# ISL6236A_DEMO.net
KiCad netlist of a schematic drawn in Altium Designer
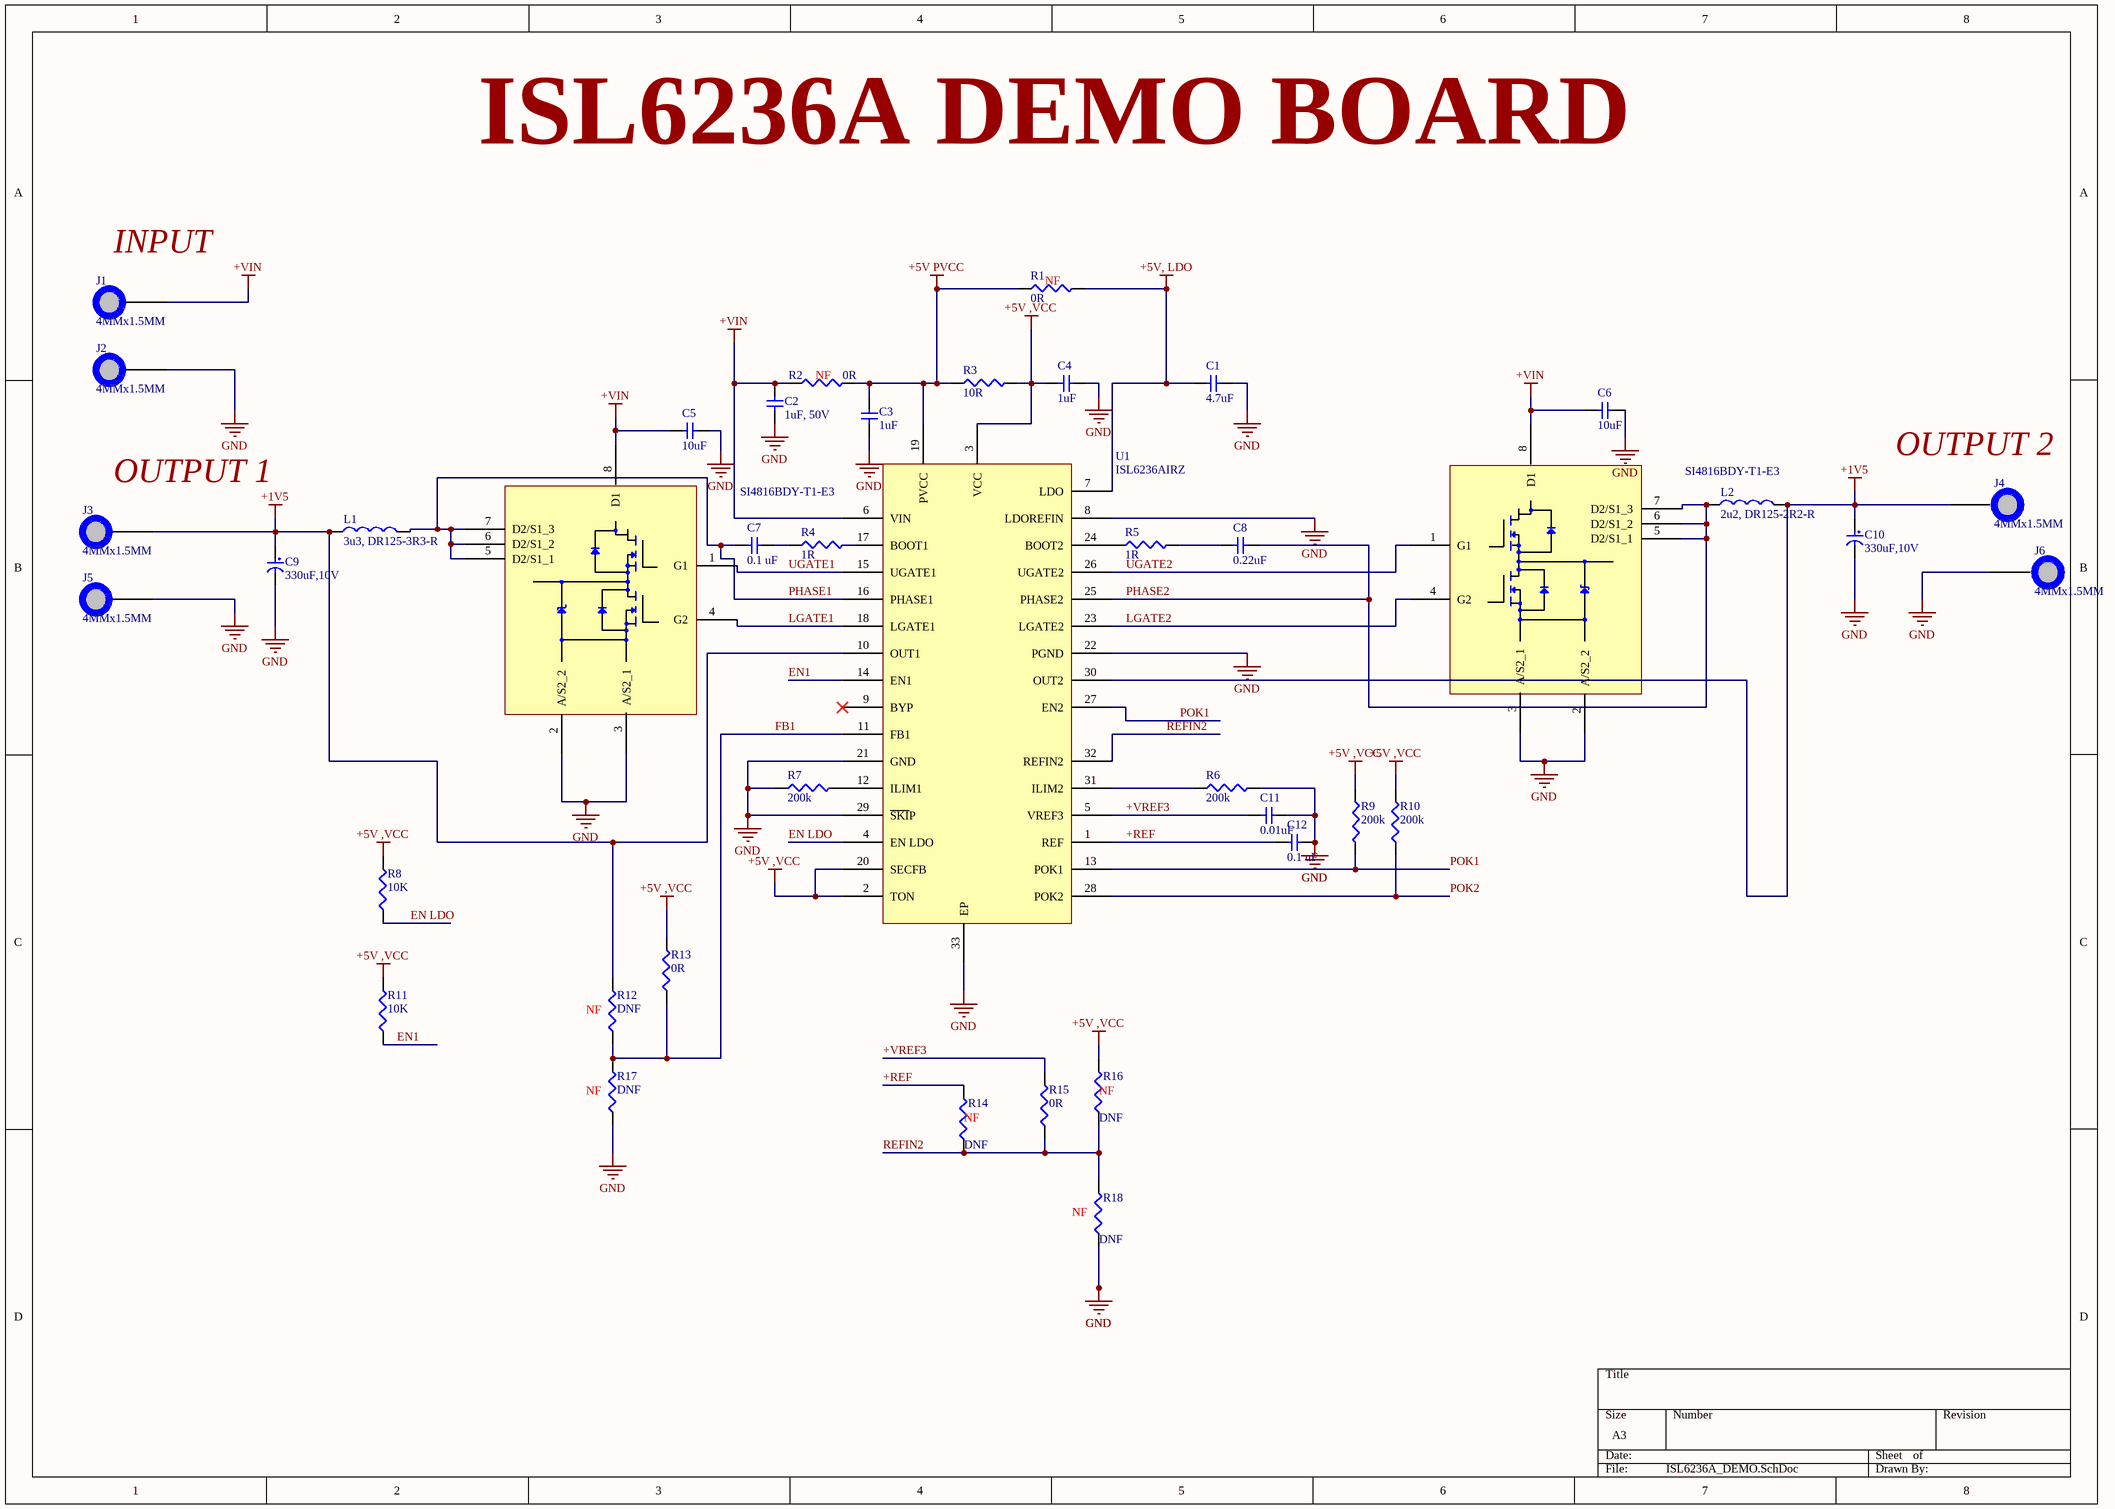
[diagram p0: ISL6236A_DEMO.SchDoc]

(export (version "E")
  (design (tool "Eeschema 10.0.6"))
  (components
    (comp (ref "C1")
      (value "4.7uF")
      (footprint "C1206")
      (description "C Series 1206 4.7 uF 50 V ±10 % Tolerance X5R SMT Multilayer Ceramic Capacitor")
      (fields
        (field (name "MANUFACTURER") "TDK")
        (field (name "MANUFACTURER PART NUMBER") "C3216X5R1H475K160AB")
      )
      (libsource (lib "ISL6236A_DEMO_V1I1") (part "C3216X5R1H475K160AB"))
    )
    (comp (ref "C2")
      (value "1uF, 50V")
      (footprint "C0805")
      (fields
        (field (name "MANUFACTURER") "KEMET")
        (field (name "MANUFACTURER PART NUMBER") "C0805X105K5RACAUTO")
      )
      (libsource (lib "ISL6236A_DEMO_V1I1") (part "C0805X105K5RACAUTO"))
    )
    (comp (ref "C3")
      (value "1uF")
      (footprint "C0805")
      (description "Cap Cer 1UF 25V X5R 0805")
      (fields
        (field (name "MANUFACTURER") "Kyocera AVX")
        (field (name "MANUFACTURER PART NUMBER") "08053D105KAT2~{A}3K")
      )
      (libsource (lib "ISL6236A_DEMO_V1I1") (part "08053D105KAT2A{backslash}3K"))
    )
    (comp (ref "C4")
      (value "1uF")
      (footprint "C0805")
      (description "Cap Cer 1UF 25V X5R 0805")
      (fields
        (field (name "MANUFACTURER") "Kyocera AVX")
        (field (name "MANUFACTURER PART NUMBER") "08053D105KAT2~{A}3K")
      )
      (libsource (lib "ISL6236A_DEMO_V1I1") (part "08053D105KAT2A{backslash}3K"))
    )
    (comp (ref "C5")
      (value "10uF")
      (footprint "C1210")
      (description "Cap Ceramic 10uF 50V X5R 10% Pad SMD 1210 85C T/R")
      (fields
        (field (name "MANUFACTURER") "KEMET")
        (field (name "MANUFACTURER PART NUMBER") "C1210C106K5PAC7210")
      )
      (libsource (lib "ISL6236A_DEMO_V1I1") (part "C1210C106K5PAC7210"))
    )
    (comp (ref "C6")
      (value "10uF")
      (footprint "C1210")
      (description "Cap Ceramic 10uF 50V X5R 10% Pad SMD 1210 85C T/R")
      (fields
        (field (name "MANUFACTURER") "KEMET")
        (field (name "MANUFACTURER PART NUMBER") "C1210C106K5PAC7210")
      )
      (libsource (lib "ISL6236A_DEMO_V1I1") (part "C1210C106K5PAC7210"))
    )
    (comp (ref "C7")
      (value "0.1 uF")
      (footprint "C0805")
      (description "Multilayer Ceramic Capacitor, 0.1 uF, 50 V, ± 10%, X7R, 0805 [2012 Metric]")
      (fields
        (field (name "MANUFACTURER") "KEMET")
        (field (name "MANUFACTURER PART NUMBER") "C0805C104K5RAC7800")
      )
      (libsource (lib "ISL6236A_DEMO_V1I1") (part "C0805C104K5RAC7800"))
    )
    (comp (ref "C8")
      (value "0.22uF")
      (footprint "C0805")
      (description "Multilayer Ceramic Capacitor, 0.22 uF, 50 V, ± 10%, X7R, 0805 [2012 Metric]")
      (fields
        (field (name "MANUFACTURER") "KEMET")
        (field (name "MANUFACTURER PART NUMBER") "C0805C224K5RACTU")
      )
      (libsource (lib "ISL6236A_DEMO_V1I1") (part "C0805C224K5RACTU"))
    )
    (comp (ref "C9")
      (value "330uF,10V")
      (footprint "7343-43")
      (description "Cap Tant Solid 330uF 10V X CASE 20% (7.3 X 4.3 X 4mm) SMD 7343-43 0.004 Ohm 125 C T/R")
      (fields
        (field (name "MANUFACTURER") "KEMET")
        (field (name "MANUFACTURER PART NUMBER") "T530X337M010ATE004")
      )
      (libsource (lib "ISL6236A_DEMO_V1I1") (part "T530X337M010ATE004"))
    )
    (comp (ref "C10")
      (value "330uF,10V")
      (footprint "7343-43")
      (description "Cap Tant Solid 330uF 10V X CASE 20% (7.3 X 4.3 X 4mm) SMD 7343-43 0.004 Ohm 125 C T/R")
      (fields
        (field (name "MANUFACTURER") "KEMET")
        (field (name "MANUFACTURER PART NUMBER") "T530X337M010ATE004")
      )
      (libsource (lib "ISL6236A_DEMO_V1I1") (part "T530X337M010ATE004"))
    )
    (comp (ref "C11")
      (value "0.01uF")
      (footprint "C0805")
      (description "0805 C 10nF Ceramic Multilayer Capacitor; 50 VDC; +125degC; X7R Dielec; +/-10%")
      (fields
        (field (name "MANUFACTURER") "KEMET")
        (field (name "MANUFACTURER PART NUMBER") "C0805F103K5RACTU")
      )
      (libsource (lib "ISL6236A_DEMO_V1I1") (part "C0805F103K5RACTU"))
    )
    (comp (ref "C12")
      (value "0.1 uF")
      (footprint "C0805")
      (description "Multilayer Ceramic Capacitor, 0.1 uF, 50 V, ± 10%, X7R, 0805 [2012 Metric]")
      (fields
        (field (name "MANUFACTURER") "KEMET")
        (field (name "MANUFACTURER PART NUMBER") "C0805C104K5RAC7800")
      )
      (libsource (lib "ISL6236A_DEMO_V1I1") (part "C0805C104K5RAC7800"))
    )
    (comp (ref "J1")
      (value "4MMx1.5MM")
      (footprint "PAD_WITH_HOLE_4MMx1MM5")
      (description "Pad with a hole 4mmx1.5mm")
      (libsource (lib "ISL6236A_DEMO") (part "PAD_WITH_HOLE_4MMx1MM5"))
    )
    (comp (ref "J2")
      (value "4MMx1.5MM")
      (footprint "PAD_WITH_HOLE_4MMx1MM5")
      (description "Pad with a hole 4mmx1.5mm")
      (libsource (lib "ISL6236A_DEMO") (part "PAD_WITH_HOLE_4MMx1MM5"))
    )
    (comp (ref "J3")
      (value "4MMx1.5MM")
      (footprint "PAD_WITH_HOLE_4MMx1MM5")
      (description "Pad with a hole 4mmx1.5mm")
      (libsource (lib "ISL6236A_DEMO") (part "PAD_WITH_HOLE_4MMx1MM5"))
    )
    (comp (ref "J4")
      (value "4MMx1.5MM")
      (footprint "PAD_WITH_HOLE_4MMx1MM5")
      (description "Pad with a hole 4mmx1.5mm")
      (libsource (lib "ISL6236A_DEMO") (part "PAD_WITH_HOLE_4MMx1MM5"))
    )
    (comp (ref "J5")
      (value "4MMx1.5MM")
      (footprint "PAD_WITH_HOLE_4MMx1MM5")
      (description "Pad with a hole 4mmx1.5mm")
      (libsource (lib "ISL6236A_DEMO") (part "PAD_WITH_HOLE_4MMx1MM5"))
    )
    (comp (ref "J6")
      (value "4MMx1.5MM")
      (footprint "PAD_WITH_HOLE_4MMx1MM5")
      (description "Pad with a hole 4mmx1.5mm")
      (libsource (lib "ISL6236A_DEMO") (part "PAD_WITH_HOLE_4MMx1MM5"))
    )
    (comp (ref "L1")
      (value "3u3, DR125-3R3-R")
      (footprint "DR125")
      (description "Inductor Power Shielded Drum Core 3.3uH 20% 100KHz Ferrite 9.26A 6.3mOhm DCR T/R")
      (fields
        (field (name "MANUFACTURER") "Eaton Cooper")
        (field (name "MANUFACTURER PART NUMBER") "DR125-3R3-R")
      )
      (libsource (lib "ISL6236A_DEMO") (part "DR125-3R3-R"))
    )
    (comp (ref "L2")
      (value "2u2, DR125-2R2-R")
      (footprint "DR125")
      (description "Ind Power Shielded Wirewound 2.2uH 20% 100KHz Ferrite 10.9A T/R")
      (fields
        (field (name "MANUFACTURER") "Eaton Cooper")
        (field (name "MANUFACTURER PART NUMBER") "DR125-2R2-R")
      )
      (libsource (lib "ISL6236A_DEMO") (part "DR125-2R2-R"))
    )
    (comp (ref "Q1")
      (value "SI4816BDY-T1-E3")
      (footprint "SO-8")
      (description "Trans Mosfet N-ch 30V 5.8A/8.2A 8-PIN SOIC N T/r")
      (fields (field (name "MANUFACTURER") "Vishay Siliconix"))
      (libsource (lib "ISL6236A_DEMO") (part "SI4816BDY-T1-E3"))
    )
    (comp (ref "Q2")
      (value "SI4816BDY-T1-E3")
      (footprint "SO-8")
      (description "Trans Mosfet N-ch 30V 5.8A/8.2A 8-PIN SOIC N T/r")
      (fields (field (name "MANUFACTURER") "Vishay Siliconix"))
      (libsource (lib "ISL6236A_DEMO") (part "SI4816BDY-T1-E3"))
    )
    (comp (ref "R1")
      (value "0R")
      (footprint "R0805")
      (description "Fixed Resistor, Metal Glaze/thick Film, 0.125W, 0ohm, Surface Mount, 0805")
      (fields
        (field (name "MANUFACTURER") "Yageo")
        (field (name "MANUFACTURER PART NUMBER") "AC0805JR-070RL")
      )
      (libsource (lib "ISL6236A_DEMO_V1I1") (part "AC0805JR-070RL"))
    )
    (comp (ref "R2")
      (value "0R")
      (footprint "R0805")
      (description "Fixed Resistor, Metal Glaze/thick Film, 0.125W, 0ohm, Surface Mount, 0805")
      (fields
        (field (name "MANUFACTURER") "Yageo")
        (field (name "MANUFACTURER PART NUMBER") "AC0805JR-070RL")
      )
      (libsource (lib "ISL6236A_DEMO_V1I1") (part "AC0805JR-070RL"))
    )
    (comp (ref "R3")
      (value "10R")
      (footprint "R0805")
      (description "Res Thick Film 0805 10 Ohm 1% 0.125W(1/8W) ±200ppm/C Pad SMD Automotive T/R")
      (fields
        (field (name "MANUFACTURER") "Yageo")
        (field (name "MANUFACTURER PART NUMBER") "AC0805FR-0710RL")
      )
      (libsource (lib "ISL6236A_DEMO") (part "AC0805FR-0710RL"))
    )
    (comp (ref "R4")
      (value "1R")
      (footprint "R0805")
      (description "Res Thick Film 0805 1 Ohm 1% 0.125W(1/8W) ±200ppm/C Pad SMD Automotive T/R")
      (fields
        (field (name "MANUFACTURER") "Yageo")
        (field (name "MANUFACTURER PART NUMBER") "AC0805FR-071RL")
      )
      (libsource (lib "ISL6236A_DEMO") (part "AC0805FR-071RL"))
    )
    (comp (ref "R5")
      (value "1R")
      (footprint "R0805")
      (description "Res Thick Film 0805 1 Ohm 1% 0.125W(1/8W) ±200ppm/C Pad SMD Automotive T/R")
      (fields
        (field (name "MANUFACTURER") "Yageo")
        (field (name "MANUFACTURER PART NUMBER") "AC0805FR-071RL")
      )
      (libsource (lib "ISL6236A_DEMO") (part "AC0805FR-071RL"))
    )
    (comp (ref "R6")
      (value "200k")
      (footprint "R0805")
      (description "Res Thick Film 0805 200K Ohm 1% 0.125W(1/8W) ±100ppm/C Pad SMD Automotive T/R")
      (fields
        (field (name "MANUFACTURER") "Yageo")
        (field (name "MANUFACTURER PART NUMBER") "AC0805FR-07200KL")
      )
      (libsource (lib "ISL6236A_DEMO") (part "AC0805FR-07200KL"))
    )
    (comp (ref "R7")
      (value "200k")
      (footprint "R0805")
      (description "Res Thick Film 0805 200K Ohm 1% 0.125W(1/8W) ±100ppm/C Pad SMD Automotive T/R")
      (fields
        (field (name "MANUFACTURER") "Yageo")
        (field (name "MANUFACTURER PART NUMBER") "AC0805FR-07200KL")
      )
      (libsource (lib "ISL6236A_DEMO") (part "AC0805FR-07200KL"))
    )
    (comp (ref "R8")
      (value "10K")
      (footprint "R0805")
      (description "Res Thick Film 0805 10K Ohm 1% 0.125W(1/8W) ±100ppm/C Pad SMD Automotive T/R")
      (fields
        (field (name "MANUFACTURER") "Yageo")
        (field (name "MANUFACTURER PART NUMBER") "AC0805FR-0710KL")
      )
      (libsource (lib "ISL6236A_DEMO") (part "AC0805FR-0710KL"))
    )
    (comp (ref "R9")
      (value "200k")
      (footprint "R0805")
      (description "Res Thick Film 0805 200K Ohm 1% 0.125W(1/8W) ±100ppm/C Pad SMD Automotive T/R")
      (fields
        (field (name "MANUFACTURER") "Yageo")
        (field (name "MANUFACTURER PART NUMBER") "AC0805FR-07200KL")
      )
      (libsource (lib "ISL6236A_DEMO") (part "AC0805FR-07200KL"))
    )
    (comp (ref "R10")
      (value "200k")
      (footprint "R0805")
      (description "Res Thick Film 0805 200K Ohm 1% 0.125W(1/8W) ±100ppm/C Pad SMD Automotive T/R")
      (fields
        (field (name "MANUFACTURER") "Yageo")
        (field (name "MANUFACTURER PART NUMBER") "AC0805FR-07200KL")
      )
      (libsource (lib "ISL6236A_DEMO") (part "AC0805FR-07200KL"))
    )
    (comp (ref "R11")
      (value "10K")
      (footprint "R0805")
      (description "Res Thick Film 0805 10K Ohm 1% 0.125W(1/8W) ±100ppm/C Pad SMD Automotive T/R")
      (fields
        (field (name "MANUFACTURER") "Yageo")
        (field (name "MANUFACTURER PART NUMBER") "AC0805FR-0710KL")
      )
      (libsource (lib "ISL6236A_DEMO") (part "AC0805FR-0710KL"))
    )
    (comp (ref "R12") (value "DNF") (footprint "R0805") (libsource (lib "ISL6236A_DEMO") (part "RES")))
    (comp (ref "R13")
      (value "0R")
      (footprint "R0805")
      (description "Fixed Resistor, Metal Glaze/thick Film, 0.125W, 0ohm, Surface Mount, 0805")
      (fields
        (field (name "MANUFACTURER") "Yageo")
        (field (name "MANUFACTURER PART NUMBER") "AC0805JR-070RL")
      )
      (libsource (lib "ISL6236A_DEMO_V1I1") (part "AC0805JR-070RL"))
    )
    (comp (ref "R14") (value "DNF") (footprint "R0805") (libsource (lib "ISL6236A_DEMO") (part "RES")))
    (comp (ref "R15")
      (value "0R")
      (footprint "R0805")
      (description "Fixed Resistor, Metal Glaze/thick Film, 0.125W, 0ohm, Surface Mount, 0805")
      (fields
        (field (name "MANUFACTURER") "Yageo")
        (field (name "MANUFACTURER PART NUMBER") "AC0805JR-070RL")
      )
      (libsource (lib "ISL6236A_DEMO_V1I1") (part "AC0805JR-070RL"))
    )
    (comp (ref "R16") (value "DNF") (footprint "R0805") (libsource (lib "ISL6236A_DEMO") (part "RES")))
    (comp (ref "R17") (value "DNF") (footprint "R0805") (libsource (lib "ISL6236A_DEMO") (part "RES")))
    (comp (ref "R18") (value "DNF") (footprint "R0805") (libsource (lib "ISL6236A_DEMO") (part "RES")))
    (comp (ref "U1")
      (value "ISL6236AIRZ")
      (footprint "L32.5x5B")
      (description "Soft Sw PWM Cntrlr 2-OUT Power Supply Controller 200KHz/300KHz/400KHz/500KHz 32-Pin QFN EP")
      (fields (field (name "MANUFACTURER") "Renesas"))
      (libsource (lib "ISL6236A_DEMO") (part "ISL6236AIRZ"))
    )
  )
  (nets
    (net (code "1") (name "+1V5") (class "Default")
      (node (ref "C10") (pin "1") (pinfunction "1_1") (pintype "passive"))
      (node (ref "C9") (pin "1") (pinfunction "1_1") (pintype "passive"))
      (node (ref "J3") (pin "1") (pinfunction "1_1") (pintype "passive"))
      (node (ref "J4") (pin "1") (pinfunction "1_1") (pintype "passive"))
      (node (ref "L1") (pin "1") (pinfunction "1_1") (pintype "passive"))
      (node (ref "L2") (pin "2") (pinfunction "2_2") (pintype "passive"))
      (node (ref "R12") (pin "2") (pinfunction "2_2") (pintype "passive"))
      (node (ref "U1") (pin "10") (pinfunction "OUT1_10") (pintype "passive"))
      (node (ref "U1") (pin "30") (pinfunction "OUT2_30") (pintype "passive"))
    )
    (net (code "2") (name "+5V ,VCC") (class "Default")
      (node (ref "C4") (pin "1") (pinfunction "1_1") (pintype "passive"))
      (node (ref "R10") (pin "2") (pinfunction "2_2") (pintype "passive"))
      (node (ref "R11") (pin "2") (pinfunction "2_2") (pintype "passive"))
      (node (ref "R13") (pin "2") (pinfunction "2_2") (pintype "passive"))
      (node (ref "R16") (pin "2") (pinfunction "2_2") (pintype "passive"))
      (node (ref "R3") (pin "2") (pinfunction "2_2") (pintype "passive"))
      (node (ref "R8") (pin "2") (pinfunction "2_2") (pintype "passive"))
      (node (ref "R9") (pin "1") (pinfunction "1_1") (pintype "passive"))
      (node (ref "U1") (pin "2") (pinfunction "TON_2") (pintype "passive"))
      (node (ref "U1") (pin "20") (pinfunction "SECFB_20") (pintype "passive"))
      (node (ref "U1") (pin "3") (pinfunction "VCC_3") (pintype "passive"))
    )
    (net (code "3") (name "+5V PVCC") (class "Default")
      (node (ref "C3") (pin "2") (pinfunction "2_2") (pintype "passive"))
      (node (ref "R1") (pin "1") (pinfunction "1_1") (pintype "passive"))
      (node (ref "R2") (pin "2") (pinfunction "2_2") (pintype "passive"))
      (node (ref "R3") (pin "1") (pinfunction "1_1") (pintype "passive"))
      (node (ref "U1") (pin "19") (pinfunction "PVCC_19") (pintype "passive"))
    )
    (net (code "4") (name "+5V, LDO") (class "Default")
      (node (ref "C1") (pin "1") (pinfunction "1_1") (pintype "passive"))
      (node (ref "R1") (pin "2") (pinfunction "2_2") (pintype "passive"))
      (node (ref "U1") (pin "7") (pinfunction "LDO_7") (pintype "passive"))
    )
    (net (code "5") (name "+VIN") (class "Default")
      (node (ref "C2") (pin "1") (pinfunction "1_1") (pintype "passive"))
      (node (ref "C5") (pin "2") (pinfunction "2_2") (pintype "passive"))
      (node (ref "C6") (pin "2") (pinfunction "2_2") (pintype "passive"))
      (node (ref "J1") (pin "1") (pinfunction "1_1") (pintype "passive"))
      (node (ref "Q1") (pin "8") (pinfunction "D1_8") (pintype "passive"))
      (node (ref "Q2") (pin "8") (pinfunction "D1_8") (pintype "passive"))
      (node (ref "R2") (pin "1") (pinfunction "1_1") (pintype "passive"))
      (node (ref "U1") (pin "6") (pinfunction "VIN_6") (pintype "passive"))
    )
    (net (code "6") (name "/+REF") (class "Default")
      (node (ref "C12") (pin "1") (pinfunction "1_1") (pintype "passive"))
      (node (ref "R14") (pin "2") (pinfunction "2_2") (pintype "passive"))
      (node (ref "U1") (pin "1") (pinfunction "REF_1") (pintype "passive"))
    )
    (net (code "7") (name "/+VREF3") (class "Default")
      (node (ref "C11") (pin "1") (pinfunction "1_1") (pintype "passive"))
      (node (ref "R15") (pin "2") (pinfunction "2_2") (pintype "passive"))
      (node (ref "U1") (pin "5") (pinfunction "VREF3_5") (pintype "passive"))
    )
    (net (code "8") (name "/EN LDO") (class "Default")
      (node (ref "R8") (pin "1") (pinfunction "1_1") (pintype "passive"))
      (node (ref "U1") (pin "4") (pinfunction "EN_LDO_4") (pintype "passive"))
    )
    (net (code "9") (name "/EN1") (class "Default")
      (node (ref "R11") (pin "1") (pinfunction "1_1") (pintype "passive"))
      (node (ref "U1") (pin "14") (pinfunction "EN1_14") (pintype "passive"))
    )
    (net (code "10") (name "/FB1") (class "Default")
      (node (ref "R12") (pin "1") (pinfunction "1_1") (pintype "passive"))
      (node (ref "R13") (pin "1") (pinfunction "1_1") (pintype "passive"))
      (node (ref "R17") (pin "2") (pinfunction "2_2") (pintype "passive"))
      (node (ref "U1") (pin "11") (pinfunction "FB1_11") (pintype "passive"))
    )
    (net (code "11") (name "/LGATE1") (class "Default")
      (node (ref "Q1") (pin "4") (pinfunction "G2_4") (pintype "passive"))
      (node (ref "U1") (pin "18") (pinfunction "LGATE1_18") (pintype "passive"))
    )
    (net (code "12") (name "/LGATE2") (class "Default")
      (node (ref "Q2") (pin "4") (pinfunction "G2_4") (pintype "passive"))
      (node (ref "U1") (pin "23") (pinfunction "LGATE2_23") (pintype "passive"))
    )
    (net (code "13") (name "/PHASE1") (class "Default")
      (node (ref "C7") (pin "1") (pinfunction "1_1") (pintype "passive"))
      (node (ref "L1") (pin "2") (pinfunction "2_2") (pintype "passive"))
      (node (ref "Q1") (pin "5") (pinfunction "D2/S1_1_5") (pintype "passive"))
      (node (ref "Q1") (pin "6") (pinfunction "D2/S1_2_6") (pintype "passive"))
      (node (ref "Q1") (pin "7") (pinfunction "D2/S1_3_7") (pintype "passive"))
      (node (ref "U1") (pin "16") (pinfunction "PHASE1_16") (pintype "passive"))
    )
    (net (code "14") (name "/PHASE2") (class "Default")
      (node (ref "C8") (pin "2") (pinfunction "2_2") (pintype "passive"))
      (node (ref "L2") (pin "1") (pinfunction "1_1") (pintype "passive"))
      (node (ref "Q2") (pin "5") (pinfunction "D2/S1_1_5") (pintype "passive"))
      (node (ref "Q2") (pin "6") (pinfunction "D2/S1_2_6") (pintype "passive"))
      (node (ref "Q2") (pin "7") (pinfunction "D2/S1_3_7") (pintype "passive"))
      (node (ref "U1") (pin "25") (pinfunction "PHASE2_25") (pintype "passive"))
    )
    (net (code "15") (name "/POK1") (class "Default")
      (node (ref "R9") (pin "2") (pinfunction "2_2") (pintype "passive"))
      (node (ref "U1") (pin "13") (pinfunction "POK1_13") (pintype "passive"))
      (node (ref "U1") (pin "27") (pinfunction "EN2_27") (pintype "passive"))
    )
    (net (code "16") (name "/POK2") (class "Default")
      (node (ref "R10") (pin "1") (pinfunction "1_1") (pintype "passive"))
      (node (ref "U1") (pin "28") (pinfunction "POK2_28") (pintype "passive"))
    )
    (net (code "17") (name "/REFIN2") (class "Default")
      (node (ref "R14") (pin "1") (pinfunction "1_1") (pintype "passive"))
      (node (ref "R15") (pin "1") (pinfunction "1_1") (pintype "passive"))
      (node (ref "R16") (pin "1") (pinfunction "1_1") (pintype "passive"))
      (node (ref "R18") (pin "2") (pinfunction "2_2") (pintype "passive"))
      (node (ref "U1") (pin "32") (pinfunction "REFIN2_32") (pintype "passive"))
    )
    (net (code "18") (name "/UGATE1") (class "Default")
      (node (ref "Q1") (pin "1") (pinfunction "G1_1") (pintype "passive"))
      (node (ref "U1") (pin "15") (pinfunction "UGATE1_15") (pintype "passive"))
    )
    (net (code "19") (name "/UGATE2") (class "Default")
      (node (ref "Q2") (pin "1") (pinfunction "G1_1") (pintype "passive"))
      (node (ref "U1") (pin "26") (pinfunction "UGATE2_26") (pintype "passive"))
    )
    (net (code "20") (name "GND") (class "Default")
      (node (ref "C1") (pin "2") (pinfunction "2_2") (pintype "passive"))
      (node (ref "C10") (pin "2") (pinfunction "2_2") (pintype "passive"))
      (node (ref "C11") (pin "2") (pinfunction "2_2") (pintype "passive"))
      (node (ref "C12") (pin "2") (pinfunction "2_2") (pintype "passive"))
      (node (ref "C2") (pin "2") (pinfunction "2_2") (pintype "passive"))
      (node (ref "C3") (pin "1") (pinfunction "1_1") (pintype "passive"))
      (node (ref "C4") (pin "2") (pinfunction "2_2") (pintype "passive"))
      (node (ref "C5") (pin "1") (pinfunction "1_1") (pintype "passive"))
      (node (ref "C6") (pin "1") (pinfunction "1_1") (pintype "passive"))
      (node (ref "C9") (pin "2") (pinfunction "2_2") (pintype "passive"))
      (node (ref "J2") (pin "1") (pinfunction "1_1") (pintype "passive"))
      (node (ref "J5") (pin "1") (pinfunction "1_1") (pintype "passive"))
      (node (ref "J6") (pin "1") (pinfunction "1_1") (pintype "passive"))
      (node (ref "Q1") (pin "2") (pinfunction "A/S2_2_2") (pintype "passive"))
      (node (ref "Q1") (pin "3") (pinfunction "A/S2_1_3") (pintype "passive"))
      (node (ref "Q2") (pin "2") (pinfunction "A/S2_2_2") (pintype "passive"))
      (node (ref "Q2") (pin "3") (pinfunction "A/S2_1_3") (pintype "passive"))
      (node (ref "R17") (pin "1") (pinfunction "1_1") (pintype "passive"))
      (node (ref "R18") (pin "1") (pinfunction "1_1") (pintype "passive"))
      (node (ref "R6") (pin "2") (pinfunction "2_2") (pintype "passive"))
      (node (ref "R7") (pin "1") (pinfunction "1_1") (pintype "passive"))
      (node (ref "U1") (pin "21") (pinfunction "GND_21") (pintype "passive"))
      (node (ref "U1") (pin "22") (pinfunction "PGND_22") (pintype "passive"))
      (node (ref "U1") (pin "29") (pinfunction "~{SKI}P_29") (pintype "passive"))
      (node (ref "U1") (pin "33") (pinfunction "EP_33") (pintype "passive"))
      (node (ref "U1") (pin "8") (pinfunction "LDOREFIN_8") (pintype "passive"))
    )
    (net (code "21") (name "Net-(C7-Pad2)") (class "Default")
      (node (ref "C7") (pin "2") (pinfunction "2_2") (pintype "passive"))
      (node (ref "R4") (pin "1") (pinfunction "1_1") (pintype "passive"))
    )
    (net (code "22") (name "Net-(C8-Pad1)") (class "Default")
      (node (ref "C8") (pin "1") (pinfunction "1_1") (pintype "passive"))
      (node (ref "R5") (pin "2") (pinfunction "2_2") (pintype "passive"))
    )
    (net (code "23") (name "Net-(U1-BOOT1)") (class "Default")
      (node (ref "R4") (pin "2") (pinfunction "2_2") (pintype "passive"))
      (node (ref "U1") (pin "17") (pinfunction "BOOT1_17") (pintype "passive"))
    )
    (net (code "24") (name "Net-(U1-BOOT2)") (class "Default")
      (node (ref "R5") (pin "1") (pinfunction "1_1") (pintype "passive"))
      (node (ref "U1") (pin "24") (pinfunction "BOOT2_24") (pintype "passive"))
    )
    (net (code "25") (name "Net-(U1-ILIM1)") (class "Default")
      (node (ref "R7") (pin "2") (pinfunction "2_2") (pintype "passive"))
      (node (ref "U1") (pin "12") (pinfunction "ILIM1_12") (pintype "passive"))
    )
    (net (code "26") (name "Net-(U1-ILIM2)") (class "Default")
      (node (ref "R6") (pin "1") (pinfunction "1_1") (pintype "passive"))
      (node (ref "U1") (pin "31") (pinfunction "ILIM2_31") (pintype "passive"))
    )
    (net (code "27") (name "unconnected-(U1-BYP-Pad9)") (class "Default")
      (node (ref "U1") (pin "9") (pinfunction "BYP_9") (pintype "passive+no_connect"))
    )
  )
)
